# Master.net
KiCad netlist of a schematic drawn in Altium Designer
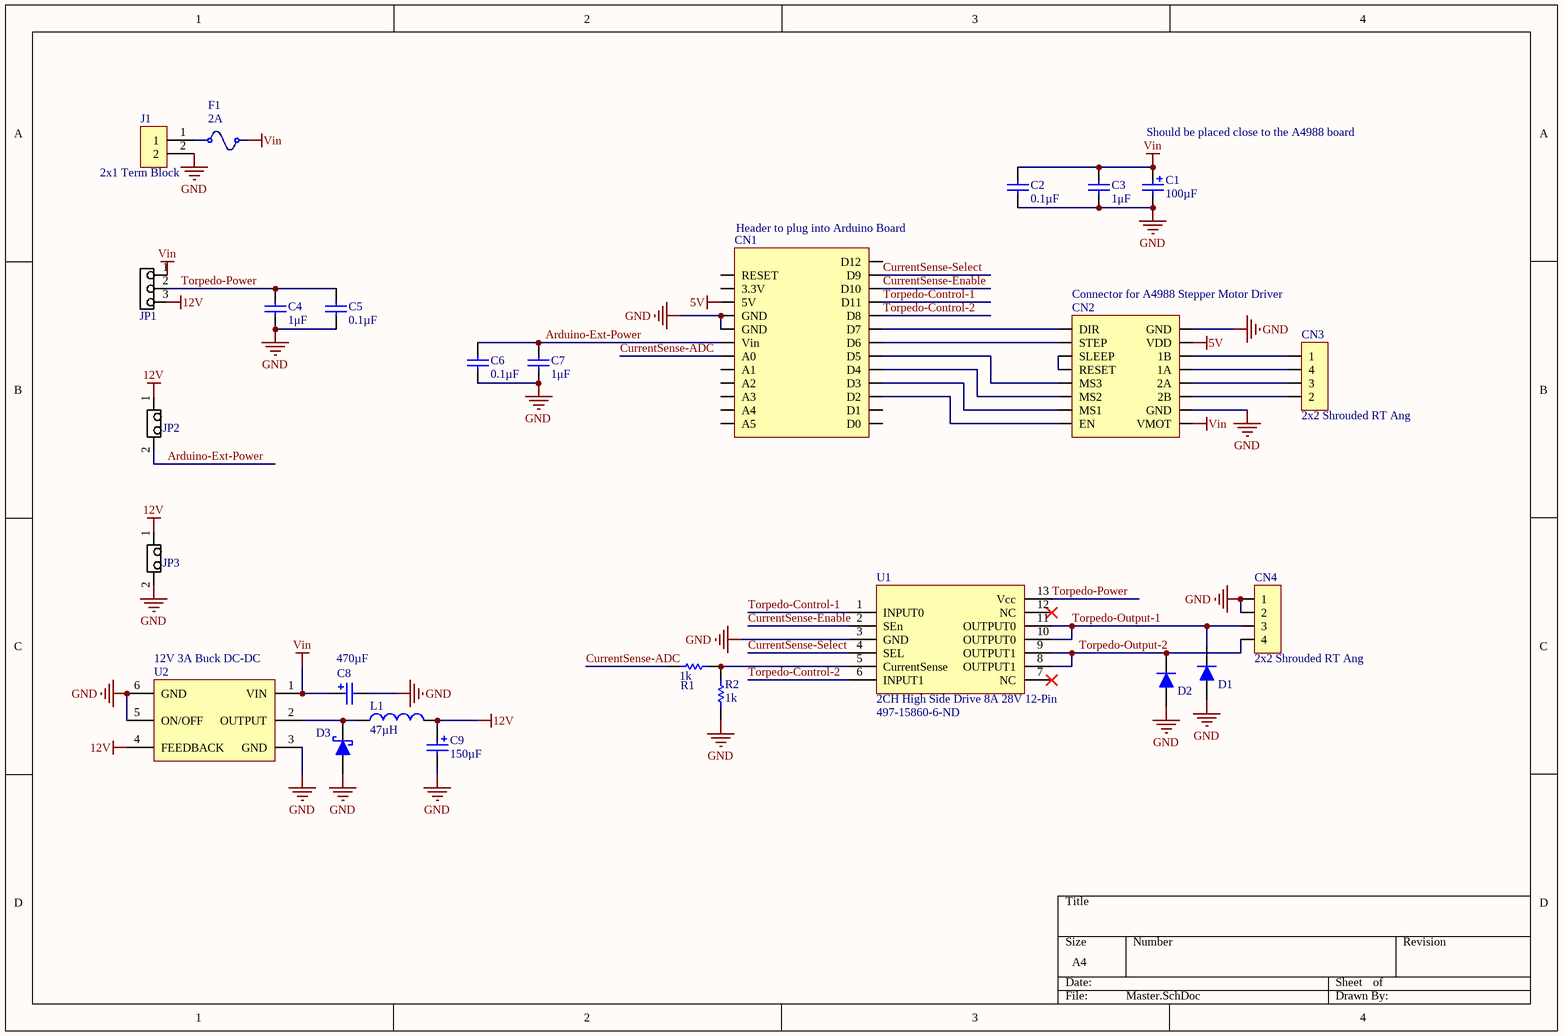
[diagram p0: Master.SchDoc]

(export (version "E")
  (design (tool "Eeschema 10.0.6"))
  (components
    (comp (ref "C1")
      (value "100µF")
      (footprint "Radial_CAN_6.6mm")
      (description "100µF 35V Aluminum Electrolytic Capacitors Radial, Can - SMD 1000 Hrs @ 105°C")
      (fields (field (name "CREATED BY") "Poorna Chander Kalidas"))
      (libsource (lib "AUVic_Integrated_Library_Capacitors") (part "100uF, 35V, 20%, Alum, SMD"))
    )
    (comp (ref "C2")
      (value "0.1uF, 50V, 10%, X7R, 0603")
      (footprint "CAPC1608N(0603\")")
      (description "0.1µF ±20% Ceramic Capacitor X7R 0603 (1608 Metric)")
      (fields (field (name "CAPACITANCE") "0.1µF") (field (name "CREATED BY") "Poorna Chander Kalidas"))
      (libsource (lib "AUVic_Integrated_Library_Capacitors") (part "0.1uF, 50V, 10%, X7R, 0603"))
    )
    (comp (ref "C3")
      (value "1μF")
      (footprint "CAPC2012N(0805\")")
      (description "1µF ±10% Ceramic Capacitor X5R 0805 (2012 Metric)")
      (fields (field (name "CREATED BY") "Poorna Chander Kalidas"))
      (libsource (lib "AUVic_Integrated_Library_Capacitors") (part "1uF 50V 0805 SMD, Ceramic"))
    )
    (comp (ref "C4")
      (value "1μF")
      (footprint "CAPC2012N(0805\")")
      (description "1µF ±10% Ceramic Capacitor X5R 0805 (2012 Metric)")
      (fields (field (name "CREATED BY") "Poorna Chander Kalidas"))
      (libsource (lib "AUVic_Integrated_Library_Capacitors") (part "1uF 50V 0805 SMD, Ceramic"))
    )
    (comp (ref "C5")
      (value "0.1uF, 50V, 10%, X7R, 0603")
      (footprint "CAPC1608N(0603\")")
      (description "0.1µF ±20% Ceramic Capacitor X7R 0603 (1608 Metric)")
      (fields (field (name "CAPACITANCE") "0.1µF") (field (name "CREATED BY") "Poorna Chander Kalidas"))
      (libsource (lib "AUVic_Integrated_Library_Capacitors") (part "0.1uF, 50V, 10%, X7R, 0603"))
    )
    (comp (ref "C6")
      (value "0.1uF, 50V, 10%, X7R, 0603")
      (footprint "CAPC1608N(0603\")")
      (description "0.1µF ±20% Ceramic Capacitor X7R 0603 (1608 Metric)")
      (fields (field (name "CAPACITANCE") "0.1µF") (field (name "CREATED BY") "Poorna Chander Kalidas"))
      (libsource (lib "AUVic_Integrated_Library_Capacitors") (part "0.1uF, 50V, 10%, X7R, 0603"))
    )
    (comp (ref "C7")
      (value "1μF")
      (footprint "CAPC2012N(0805\")")
      (description "1µF ±10% Ceramic Capacitor X5R 0805 (2012 Metric)")
      (fields (field (name "CREATED BY") "Poorna Chander Kalidas"))
      (libsource (lib "AUVic_Integrated_Library_Capacitors") (part "1uF 50V 0805 SMD, Ceramic"))
    )
    (comp (ref "C8")
      (value "470µF")
      (footprint "12.5mm Dia Radial THD")
      (description "470µF 50V Aluminum Electrolytic Capacitors Radial, Can 5000 Hrs @ 105°C")
      (fields (field (name "CREATED BY") "Poorna Chander Kalidas"))
      (libsource (lib "AUVic_Integrated_Library_Capacitors") (part "470uF, 50V, 20%, Alum, SMD"))
    )
    (comp (ref "C9")
      (value "150µF")
      (footprint "6.3mm Dia Radial SMD")
      (description "150µF 35V Aluminum Electrolytic Capacitors Radial, Can - SMD 160 mohm @ 100kHz 2000 Hrs @ 105°C")
      (fields (field (name "CREATED BY") "Poorna Chander Kalidas"))
      (libsource (lib "AUVic_Integrated_Library_Capacitors") (part "150uF, 35V, 20%, Alum, SMD"))
    )
    (comp (ref "CN1")
      (value "Header to plug into Arduino Board")
      (footprint "Arduino Shield Reduced Pin")
      (libsource (lib "AUVic_Integrated_Library_Connectors") (part "Arduino Shield Header Reduced Pin"))
    )
    (comp (ref "CN2")
      (value "Connector for A4988 Stepper Motor Driver")
      (footprint "A4988 Stepper Motor Driver Header")
      (description "Header, Female, 2x8, Pitch: 0.1\" (2.54mm),THT")
      (fields (field (name "CREATED BY") "Poorna Chander Kalidas"))
      (libsource (lib "AUVic_Integrated_Library_Connectors") (part "Connector for A4988 Stepper Motor Driver"))
    )
    (comp (ref "CN3")
      (value "2x2 Shrouded RT Ang")
      (footprint "HEADER, MALE, Shrouded, 4POS, 2MM, RT ANG,THT")
      (description "Header, Male, 2x2, Pitch: 0.1\" (2.54mm), THT")
      (fields
        (field (name "PUBLISHER") "AUVic")
        (field (name "REVIEWED BY") "*")
        (field (name "CREATED BY") "Poorna Chander Kalidas")
      )
      (libsource (lib "AUVic_Integrated_Library_Connectors") (part "Header, Male, 2x2 Conn, Shrouded, THT, 2MM RT ANG TIN"))
    )
    (comp (ref "CN4")
      (value "2x2 Shrouded RT Ang")
      (footprint "HEADER, MALE, Shrouded, 4POS, 2MM, RT ANG,THT")
      (description "Header, Male, 2x2, Pitch: 0.1\" (2.54mm), THT")
      (fields
        (field (name "PUBLISHER") "AUVic")
        (field (name "REVIEWED BY") "*")
        (field (name "CREATED BY") "Poorna Chander Kalidas")
      )
      (libsource (lib "") (part "Header, Male, 2x2 Conn, Shrouded, THT, 2MM RT ANG TIN_1"))
    )
    (comp (ref "D1")
      (value "JD 2A 600V")
      (footprint "DO-214AA")
      (description "Junction Diode 2A 600V")
      (fields (field (name "CREATED BY") "Poorna Chander Kalidas") (field (name "PUBLISHER") "AUVic"))
      (libsource (lib "AUVic_Integrated_Library_Diodes") (part "JD 2A 600V"))
    )
    (comp (ref "D2")
      (value "JD 2A 600V")
      (footprint "DO-214AA")
      (description "Junction Diode 2A 600V")
      (fields (field (name "CREATED BY") "Poorna Chander Kalidas") (field (name "PUBLISHER") "AUVic"))
      (libsource (lib "AUVic_Integrated_Library_Diodes") (part "JD 2A 600V"))
    )
    (comp (ref "D3")
      (value "TSSA5U50E3GCT-ND")
      (footprint "DO-214AC")
      (description "Diode Schottky 50V 5A Surface Mount DO-214AC (SMA)")
      (fields (field (name "CREATED BY") "Poorna Chander Kalidas"))
      (libsource (lib "AUVic_Integrated_Library_Diodes") (part "TSSA5U50E3GCT-ND"))
    )
    (comp (ref "F1")
      (value "2A")
      (footprint "1206 SMD")
      (description "SMD Fuse, 2A, 63V,")
      (fields (field (name "CREATED BY") "Poorna Chander Kalidas"))
      (libsource (lib "AUVic_Integrated_Library_Fuses") (part "SMD Fuse, 2A, 63V,"))
    )
    (comp (ref "J1")
      (value "2x1 Term Block")
      (footprint "2X1 Terminal Blocks")
      (fields (field (name "MADE BY") "Andy Bates"))
      (libsource (lib "AUVic_Integrated_Library_Connectors") (part "2x1 Terminal Block"))
    )
    (comp (ref "JP1")
      (value "1x3 Male Jumper")
      (footprint "Header, Male, 1x3, Pitch: 0.1\" (2.54mm),THT")
      (fields (field (name "MADE BY") "Poorna Chander Kalidas"))
      (libsource (lib "AUVic_Integrated_Library_Connectors") (part "1x3 Male Jumper"))
    )
    (comp (ref "JP2")
      (value "1X2 Pin Head")
      (footprint "2X1 Males Header")
      (fields (field (name "MADE BY") "Andy Bates"))
      (libsource (lib "AUVic_Integrated_Library_Connectors") (part "1x2 Male Header"))
    )
    (comp (ref "JP3")
      (value "1X2 Pin Head")
      (footprint "2X1 Males Header")
      (fields (field (name "MADE BY") "Andy Bates"))
      (libsource (lib "AUVic_Integrated_Library_Connectors") (part "1x2 Male Header"))
    )
    (comp (ref "L1")
      (value "47µH")
      (footprint "12mm SMD")
      (description "47µH Shielded Wirewound Inductor 3.8A 60 mOhm Max Nonstandard")
      (fields (field (name "CREATED BY") "Poorna Chander Kalidas"))
      (libsource (lib "AUVic_Integrated_Library_Inductors") (part "47µH 3.8A Inductor"))
    )
    (comp (ref "R1")
      (value "1k")
      (footprint "RESC1608N(0603\")")
      (description "1kR, 1%, 1/10W , 0603, SMD")
      (fields (field (name "CREATED BY") "Andy Bates") (field (name "PUBLISHER") "AUVic"))
      (libsource (lib "AUVic_Integrated_Library_Resistors") (part "1kR, 1%, 1/10W , 0603, SMD"))
    )
    (comp (ref "R2")
      (value "1k")
      (footprint "RESC1608N(0603\")")
      (description "1kR, 1%, 1/10W , 0603, SMD")
      (fields (field (name "CREATED BY") "Andy Bates") (field (name "PUBLISHER") "AUVic"))
      (libsource (lib "AUVic_Integrated_Library_Resistors") (part "1kR, 1%, 1/10W , 0603, SMD"))
    )
    (comp (ref "U1")
      (value "2CH High Side Drive 8A 28V 12-Pin")
      (footprint "PowerSSO-12")
      (description "2 Channel High Side Drive MOSFET controlable by logic signal 12-Pin")
      (fields
        (field (name "SUPPLIER PART NUMBER 1") "497-15860-6-ND")
        (field (name "CREATED BY") "Poorna Chander Kalidas")
      )
      (libsource (lib "AUVic_Integrated_Library_Transistors") (part "2CH High Side Drive 8A 28V 12-Pin"))
    )
    (comp (ref "U2")
      (value "12V 3A Buck DC-DC")
      (footprint "5-DDPAK")
      (fields (field (name "CREATED BY") "Poorna Chander Kalidas"))
      (libsource (lib "AUVic_Integrated_Library_Regulators") (part "12V 3A Buck DC-DC"))
    )
  )
  (nets
    (net (code "1") (name "/Arduino-Ext-Power") (class "Default")
      (node (ref "C6") (pin "2") (pinfunction "Cathode_2") (pintype "passive"))
      (node (ref "C7") (pin "2") (pinfunction "Cathode_2") (pintype "passive"))
      (node (ref "CN1") (pin "8") (pinfunction "Vin_8") (pintype "passive"))
      (node (ref "JP2") (pin "2") (pinfunction "2_2") (pintype "passive"))
    )
    (net (code "2") (name "/CurrentSense-ADC") (class "Default")
      (node (ref "CN1") (pin "9") (pinfunction "A0_9") (pintype "passive"))
      (node (ref "R1") (pin "1") (pinfunction "1_1") (pintype "passive"))
    )
    (net (code "3") (name "/CurrentSense-Enable") (class "Default")
      (node (ref "CN1") (pin "25") (pinfunction "D10_25") (pintype "passive"))
      (node (ref "U1") (pin "2") (pinfunction "SEn_2") (pintype "passive"))
    )
    (net (code "4") (name "/CurrentSense-Select") (class "Default")
      (node (ref "CN1") (pin "24") (pinfunction "D9_24") (pintype "passive"))
      (node (ref "U1") (pin "4") (pinfunction "SEL_4") (pintype "passive"))
    )
    (net (code "5") (name "/Torpedo-Control-1") (class "Default")
      (node (ref "CN1") (pin "26") (pinfunction "D11_26") (pintype "passive"))
      (node (ref "U1") (pin "1") (pinfunction "INPUT0_1") (pintype "passive"))
    )
    (net (code "6") (name "/Torpedo-Control-2") (class "Default")
      (node (ref "CN1") (pin "23") (pinfunction "D8_23") (pintype "passive"))
      (node (ref "U1") (pin "6") (pinfunction "INPUT1_6") (pintype "passive"))
    )
    (net (code "7") (name "/Torpedo-Output-1") (class "Default")
      (node (ref "CN4") (pin "3") (pinfunction "3_3") (pintype "passive"))
      (node (ref "D1") (pin "K") (pinfunction "Cathode_K") (pintype "passive"))
      (node (ref "U1") (pin "10") (pinfunction "OUTPUT0_10") (pintype "passive"))
      (node (ref "U1") (pin "11") (pinfunction "OUTPUT0_11") (pintype "passive"))
    )
    (net (code "8") (name "/Torpedo-Output-2") (class "Default")
      (node (ref "CN4") (pin "4") (pinfunction "4_4") (pintype "passive"))
      (node (ref "D2") (pin "K") (pinfunction "Cathode_K") (pintype "passive"))
      (node (ref "U1") (pin "8") (pinfunction "OUTPUT1_8") (pintype "passive"))
      (node (ref "U1") (pin "9") (pinfunction "OUTPUT1_9") (pintype "passive"))
    )
    (net (code "9") (name "/Torpedo-Power") (class "Default")
      (node (ref "C4") (pin "2") (pinfunction "Cathode_2") (pintype "passive"))
      (node (ref "C5") (pin "2") (pinfunction "Cathode_2") (pintype "passive"))
      (node (ref "JP1") (pin "2") (pinfunction "2_2") (pintype "passive"))
      (node (ref "U1") (pin "13") (pinfunction "Vcc_13") (pintype "passive"))
    )
    (net (code "10") (name "5V") (class "Default")
      (node (ref "CN1") (pin "5") (pinfunction "5V_5") (pintype "passive"))
      (node (ref "CN2") (pin "10") (pinfunction "VDD_10") (pintype "passive"))
    )
    (net (code "11") (name "12V") (class "Default")
      (node (ref "C9") (pin "1") (pinfunction "Anode_1") (pintype "passive"))
      (node (ref "JP1") (pin "3") (pinfunction "3_3") (pintype "passive"))
      (node (ref "JP2") (pin "1") (pinfunction "1_1") (pintype "passive"))
      (node (ref "JP3") (pin "1") (pinfunction "1_1") (pintype "passive"))
      (node (ref "L1") (pin "2") (pinfunction "2_2") (pintype "passive"))
      (node (ref "U2") (pin "4") (pinfunction "FEEDBACK_4") (pintype "passive"))
    )
    (net (code "12") (name "GND") (class "Default")
      (node (ref "C1") (pin "2") (pinfunction "Cathode_2") (pintype "passive"))
      (node (ref "C2") (pin "1") (pinfunction "Anode_1") (pintype "passive"))
      (node (ref "C3") (pin "1") (pinfunction "Anode_1") (pintype "passive"))
      (node (ref "C4") (pin "1") (pinfunction "Anode_1") (pintype "passive"))
      (node (ref "C5") (pin "1") (pinfunction "Anode_1") (pintype "passive"))
      (node (ref "C6") (pin "1") (pinfunction "Anode_1") (pintype "passive"))
      (node (ref "C7") (pin "1") (pinfunction "Anode_1") (pintype "passive"))
      (node (ref "C8") (pin "2") (pinfunction "Cathode_2") (pintype "passive"))
      (node (ref "C9") (pin "2") (pinfunction "Cathode_2") (pintype "passive"))
      (node (ref "CN1") (pin "6") (pinfunction "GND_6") (pintype "passive"))
      (node (ref "CN1") (pin "7") (pinfunction "GND_7") (pintype "passive"))
      (node (ref "CN2") (pin "15") (pinfunction "GND_15") (pintype "passive"))
      (node (ref "CN2") (pin "9") (pinfunction "GND_9") (pintype "passive"))
      (node (ref "CN4") (pin "1") (pinfunction "1_1") (pintype "passive"))
      (node (ref "CN4") (pin "2") (pinfunction "2_2") (pintype "passive"))
      (node (ref "D1") (pin "A") (pinfunction "Anode_A") (pintype "passive"))
      (node (ref "D2") (pin "A") (pinfunction "Anode_A") (pintype "passive"))
      (node (ref "D3") (pin "1") (pinfunction "Anode_1") (pintype "passive"))
      (node (ref "J1") (pin "2") (pinfunction "2_2") (pintype "passive"))
      (node (ref "JP3") (pin "2") (pinfunction "2_2") (pintype "passive"))
      (node (ref "R2") (pin "1") (pinfunction "1_1") (pintype "passive"))
      (node (ref "U1") (pin "3") (pinfunction "GND_3") (pintype "passive"))
      (node (ref "U2") (pin "3") (pinfunction "GND_3") (pintype "passive"))
      (node (ref "U2") (pin "5") (pinfunction "ON/OFF_5") (pintype "passive"))
      (node (ref "U2") (pin "6") (pinfunction "GND_6") (pintype "passive"))
    )
    (net (code "13") (name "Net-(CN1-D2)") (class "Default")
      (node (ref "CN1") (pin "17") (pinfunction "D2_17") (pintype "passive"))
      (node (ref "CN2") (pin "1") (pinfunction "EN_1") (pintype "passive"))
    )
    (net (code "14") (name "Net-(CN1-D3)") (class "Default")
      (node (ref "CN1") (pin "18") (pinfunction "D3_18") (pintype "passive"))
      (node (ref "CN2") (pin "2") (pinfunction "MS1_2") (pintype "passive"))
    )
    (net (code "15") (name "Net-(CN1-D4)") (class "Default")
      (node (ref "CN1") (pin "19") (pinfunction "D4_19") (pintype "passive"))
      (node (ref "CN2") (pin "3") (pinfunction "MS2_3") (pintype "passive"))
    )
    (net (code "16") (name "Net-(CN1-D5)") (class "Default")
      (node (ref "CN1") (pin "20") (pinfunction "D5_20") (pintype "passive"))
      (node (ref "CN2") (pin "4") (pinfunction "MS3_4") (pintype "passive"))
    )
    (net (code "17") (name "Net-(CN1-D6)") (class "Default")
      (node (ref "CN1") (pin "21") (pinfunction "D6_21") (pintype "passive"))
      (node (ref "CN2") (pin "7") (pinfunction "STEP_7") (pintype "passive"))
    )
    (net (code "18") (name "Net-(CN1-D7)") (class "Default")
      (node (ref "CN1") (pin "22") (pinfunction "D7_22") (pintype "passive"))
      (node (ref "CN2") (pin "8") (pinfunction "DIR_8") (pintype "passive"))
    )
    (net (code "19") (name "Net-(CN2-1A)") (class "Default")
      (node (ref "CN2") (pin "12") (pinfunction "1A_12") (pintype "passive"))
      (node (ref "CN3") (pin "4") (pinfunction "4_4") (pintype "passive"))
    )
    (net (code "20") (name "Net-(CN2-1B)") (class "Default")
      (node (ref "CN2") (pin "11") (pinfunction "1B_11") (pintype "passive"))
      (node (ref "CN3") (pin "1") (pinfunction "1_1") (pintype "passive"))
    )
    (net (code "21") (name "Net-(CN2-2A)") (class "Default")
      (node (ref "CN2") (pin "13") (pinfunction "2A_13") (pintype "passive"))
      (node (ref "CN3") (pin "3") (pinfunction "3_3") (pintype "passive"))
    )
    (net (code "22") (name "Net-(CN2-2B)") (class "Default")
      (node (ref "CN2") (pin "14") (pinfunction "2B_14") (pintype "passive"))
      (node (ref "CN3") (pin "2") (pinfunction "2_2") (pintype "passive"))
    )
    (net (code "23") (name "Net-(CN2-RESET)") (class "Default")
      (node (ref "CN2") (pin "5") (pinfunction "RESET_5") (pintype "passive"))
      (node (ref "CN2") (pin "6") (pinfunction "SLEEP_6") (pintype "passive"))
    )
    (net (code "24") (name "Net-(D3-Cathode)") (class "Default")
      (node (ref "D3") (pin "2") (pinfunction "Cathode_2") (pintype "passive"))
      (node (ref "L1") (pin "1") (pinfunction "1_1") (pintype "passive"))
      (node (ref "U2") (pin "2") (pinfunction "OUTPUT_2") (pintype "passive"))
    )
    (net (code "25") (name "Net-(F1-Pad1)") (class "Default")
      (node (ref "F1") (pin "1") (pinfunction "1_1") (pintype "passive"))
      (node (ref "J1") (pin "1") (pinfunction "1_1") (pintype "passive"))
    )
    (net (code "26") (name "Net-(U1-CurrentSense)") (class "Default")
      (node (ref "R1") (pin "2") (pinfunction "2_2") (pintype "passive"))
      (node (ref "R2") (pin "2") (pinfunction "2_2") (pintype "passive"))
      (node (ref "U1") (pin "5") (pinfunction "CurrentSense_5") (pintype "passive"))
    )
    (net (code "27") (name "Vin") (class "Default")
      (node (ref "C1") (pin "1") (pinfunction "Anode_1") (pintype "passive"))
      (node (ref "C2") (pin "2") (pinfunction "Cathode_2") (pintype "passive"))
      (node (ref "C3") (pin "2") (pinfunction "Cathode_2") (pintype "passive"))
      (node (ref "C8") (pin "1") (pinfunction "Anode_1") (pintype "passive"))
      (node (ref "CN2") (pin "16") (pinfunction "VMOT_16") (pintype "passive"))
      (node (ref "F1") (pin "2") (pinfunction "2_2") (pintype "passive"))
      (node (ref "JP1") (pin "1") (pinfunction "1_1") (pintype "passive"))
      (node (ref "U2") (pin "1") (pinfunction "VIN_1") (pintype "passive"))
    )
    (net (code "28") (name "unconnected-(CN1-3.3V-Pad4)") (class "Default")
      (node (ref "CN1") (pin "4") (pinfunction "3.3V_4") (pintype "passive"))
    )
    (net (code "29") (name "unconnected-(CN1-A1-Pad10)") (class "Default")
      (node (ref "CN1") (pin "10") (pinfunction "A1_10") (pintype "passive"))
    )
    (net (code "30") (name "unconnected-(CN1-A2-Pad11)") (class "Default")
      (node (ref "CN1") (pin "11") (pinfunction "A2_11") (pintype "passive"))
    )
    (net (code "31") (name "unconnected-(CN1-A3-Pad12)") (class "Default")
      (node (ref "CN1") (pin "12") (pinfunction "A3_12") (pintype "passive"))
    )
    (net (code "32") (name "unconnected-(CN1-A4-Pad13)") (class "Default")
      (node (ref "CN1") (pin "13") (pinfunction "A4_13") (pintype "passive"))
    )
    (net (code "33") (name "unconnected-(CN1-A5-Pad14)") (class "Default")
      (node (ref "CN1") (pin "14") (pinfunction "A5_14") (pintype "passive"))
    )
    (net (code "34") (name "unconnected-(CN1-D0-Pad15)") (class "Default")
      (node (ref "CN1") (pin "15") (pinfunction "D0_15") (pintype "passive"))
    )
    (net (code "35") (name "unconnected-(CN1-D1-Pad16)") (class "Default")
      (node (ref "CN1") (pin "16") (pinfunction "D1_16") (pintype "passive"))
    )
    (net (code "36") (name "unconnected-(CN1-D12-Pad27)") (class "Default")
      (node (ref "CN1") (pin "27") (pinfunction "D12_27") (pintype "passive"))
    )
    (net (code "37") (name "unconnected-(CN1-RESET-Pad3)") (class "Default")
      (node (ref "CN1") (pin "3") (pinfunction "RESET_3") (pintype "passive"))
    )
    (net (code "38") (name "unconnected-(U1-NC-Pad7)") (class "Default")
      (node (ref "U1") (pin "7") (pinfunction "NC_7") (pintype "passive+no_connect"))
    )
    (net (code "39") (name "unconnected-(U1-NC-Pad12)") (class "Default")
      (node (ref "U1") (pin "12") (pinfunction "NC_12") (pintype "passive+no_connect"))
    )
  )
)
